# GRBL3-10086.net
KiCad netlist of a schematic drawn in Altium Designer
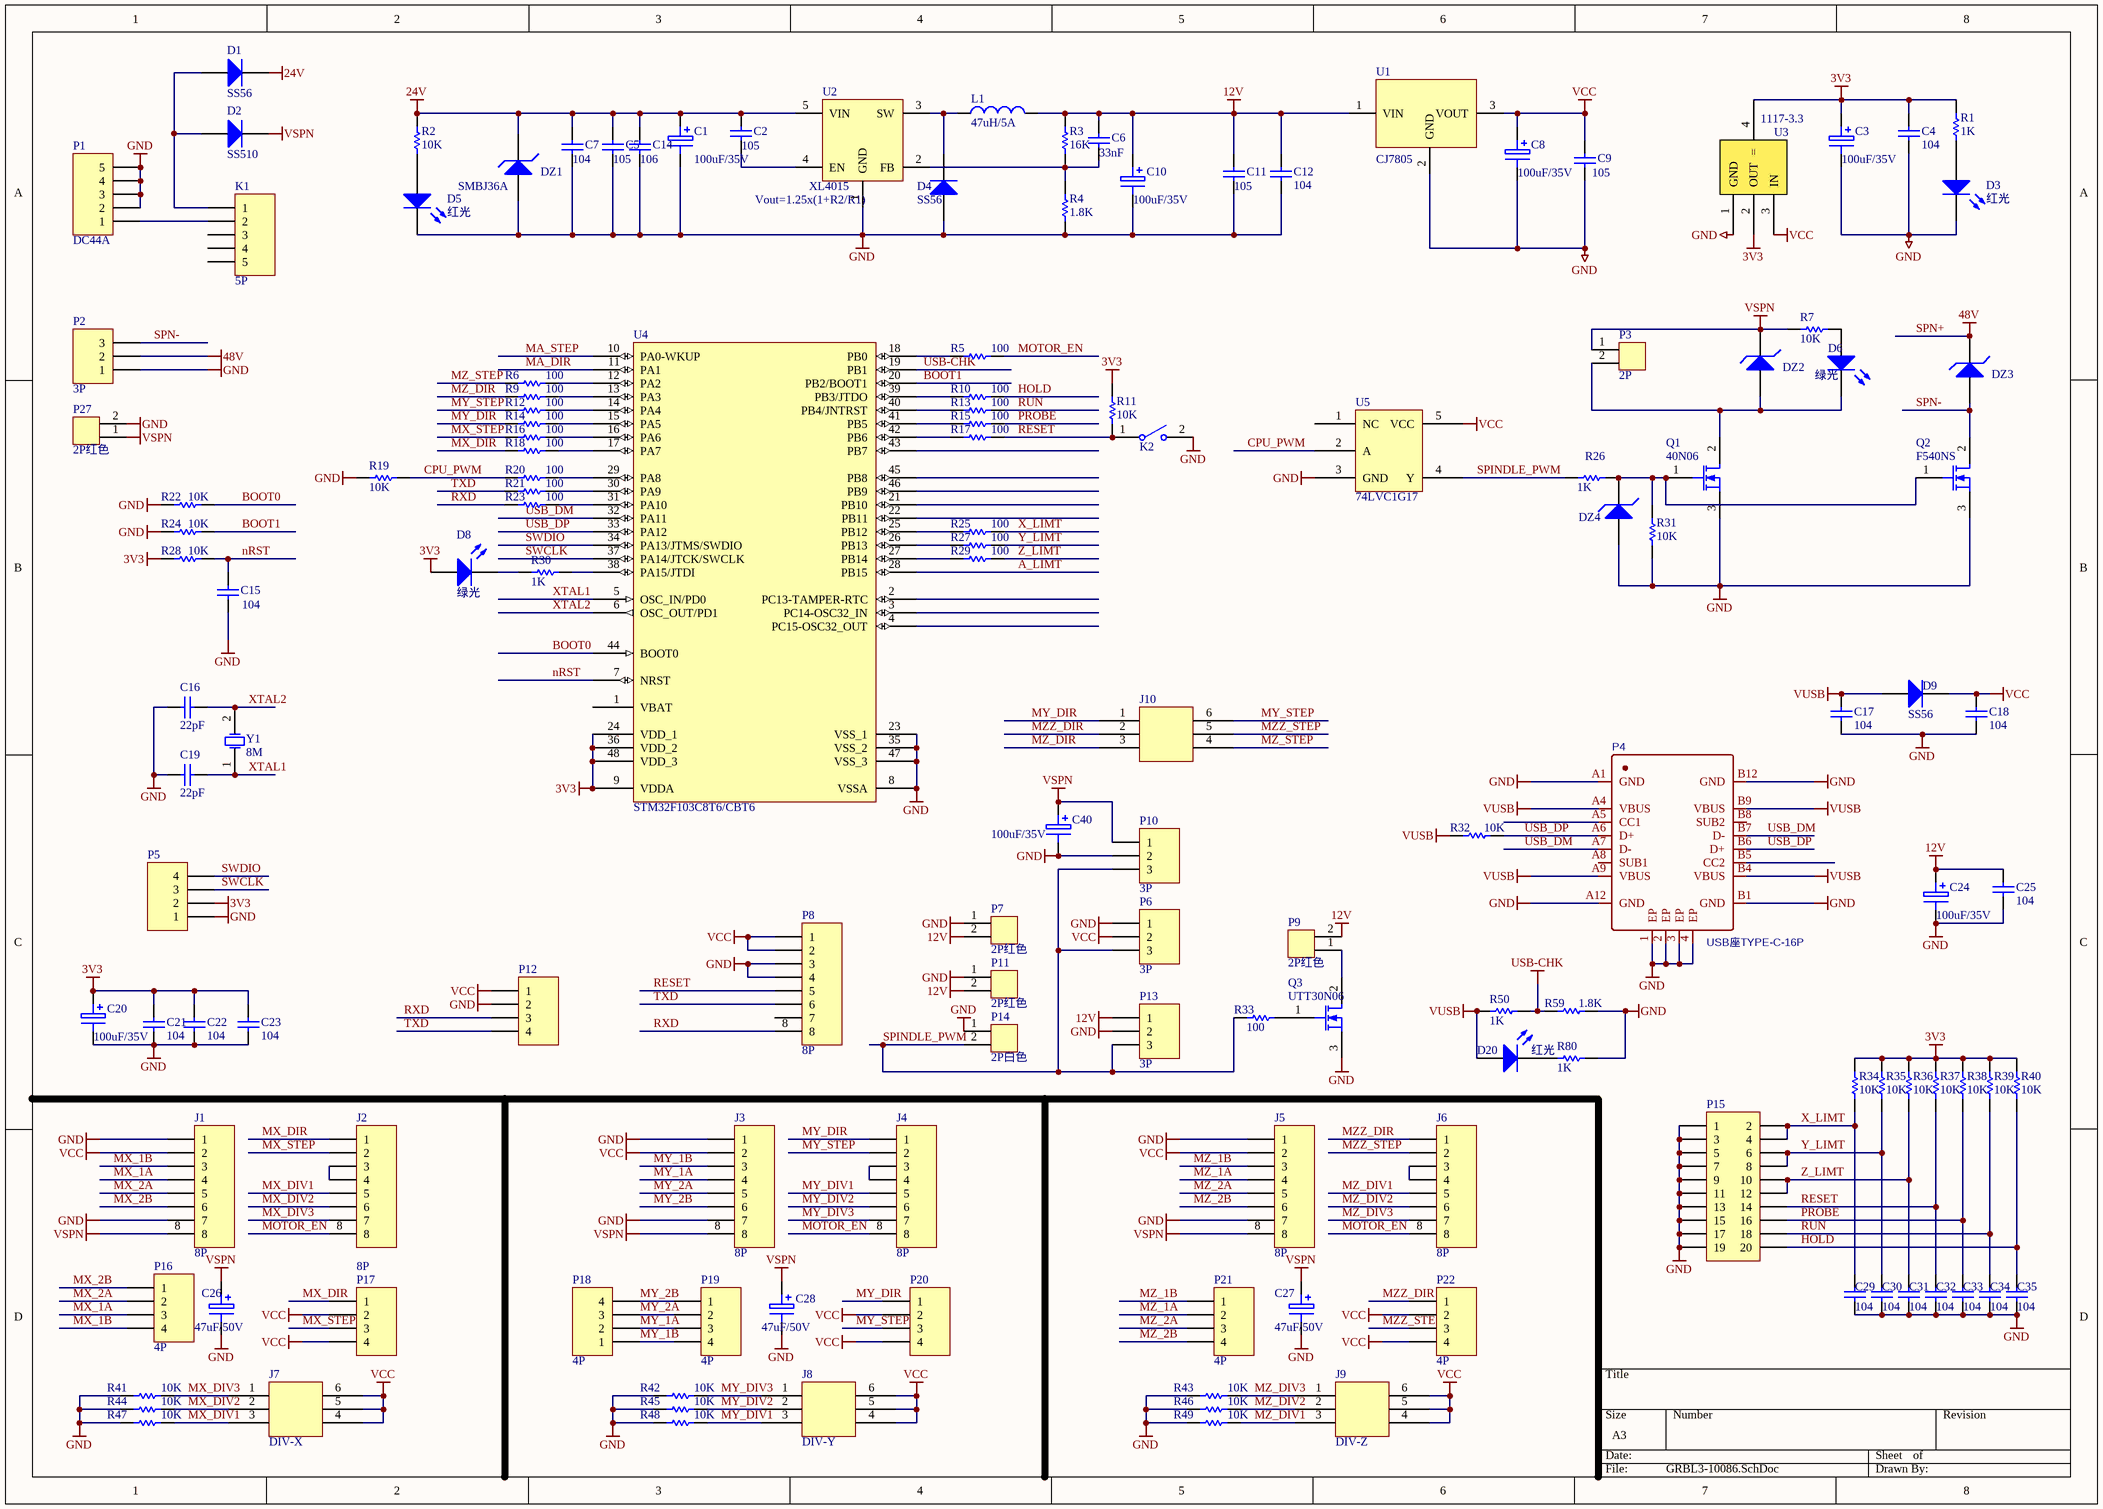
[diagram p0: GRBL3-10086.SchDoc]

(export (version "E")
  (design (tool "Eeschema 10.0.6"))
  (components
    (comp (ref "C1") (value "100uF/35V") (footprint "电解电容贴片6x6") (libsource (lib "*") (part "ELECTRO1")))
    (comp (ref "C2") (value "105") (footprint "0603C") (libsource (lib "SCH封装库") (part "CAP")))
    (comp (ref "C3") (value "100uF/35V") (footprint "电解电容贴片6x6") (libsource (lib "*") (part "ELECTRO1")))
    (comp (ref "C4")
      (value "104")
      (footprint "0603C")
      (description "Capacitor (Semiconductor SIM Model)")
      (fields (field (name "PUBLISHER") "Altium Limited"))
      (libsource (lib "Miscellaneous Devices") (part "Cap Semi"))
    )
    (comp (ref "C5") (value "105") (footprint "0603C") (libsource (lib "SCH封装库") (part "CAP")))
    (comp (ref "C6") (value "33nF") (footprint "0603C") (libsource (lib "SCH封装库") (part "CAP")))
    (comp (ref "C7") (value "104") (footprint "0603C") (libsource (lib "SCH封装库") (part "CAP")))
    (comp (ref "C8") (value "100uF/35V") (footprint "电解电容贴片6x6") (libsource (lib "*") (part "ELECTRO1")))
    (comp (ref "C9")
      (value "105")
      (footprint "0603C")
      (description "Capacitor (Semiconductor SIM Model)")
      (fields (field (name "PUBLISHER") "Altium Limited"))
      (libsource (lib "Miscellaneous Devices") (part "Cap Semi"))
    )
    (comp (ref "C10") (value "100uF/35V") (footprint "电解电容贴片6x6") (libsource (lib "*") (part "ELECTRO1")))
    (comp (ref "C11") (value "105") (footprint "0603C") (libsource (lib "SCH封装库") (part "CAP")))
    (comp (ref "C12")
      (value "104")
      (footprint "0603C")
      (description "Capacitor (Semiconductor SIM Model)")
      (fields (field (name "PUBLISHER") "Altium Limited"))
      (libsource (lib "Miscellaneous Devices") (part "Cap Semi"))
    )
    (comp (ref "C14") (value "106") (footprint "1206C") (libsource (lib "SCH封装库") (part "CAP")))
    (comp (ref "C15")
      (value "104")
      (footprint "0603C")
      (description "Capacitor (Semiconductor SIM Model)")
      (fields (field (name "PUBLISHER") "Altium Limited"))
      (libsource (lib "Miscellaneous Devices") (part "Cap Semi"))
    )
    (comp (ref "C16")
      (value "22pF")
      (footprint "0603C")
      (description "Capacitor (Semiconductor SIM Model)")
      (fields (field (name "PUBLISHER") "Altium Limited"))
      (libsource (lib "Miscellaneous Devices") (part "Cap Semi"))
    )
    (comp (ref "C17")
      (value "104")
      (footprint "0603C")
      (description "Capacitor (Semiconductor SIM Model)")
      (fields (field (name "PUBLISHER") "Altium Limited"))
      (libsource (lib "Miscellaneous Devices") (part "Cap Semi"))
    )
    (comp (ref "C18")
      (value "104")
      (footprint "0603C")
      (description "Capacitor (Semiconductor SIM Model)")
      (fields (field (name "PUBLISHER") "Altium Limited"))
      (libsource (lib "Miscellaneous Devices") (part "Cap Semi"))
    )
    (comp (ref "C19")
      (value "22pF")
      (footprint "0603C")
      (description "Capacitor (Semiconductor SIM Model)")
      (fields (field (name "PUBLISHER") "Altium Limited"))
      (libsource (lib "Miscellaneous Devices") (part "Cap Semi"))
    )
    (comp (ref "C20") (value "100uF/35V") (footprint "电解电容贴片6x6") (libsource (lib "*") (part "ELECTRO1")))
    (comp (ref "C21") (value "104") (footprint "0603C") (libsource (lib "SCH封装库") (part "CAP")))
    (comp (ref "C22") (value "104") (footprint "0603C") (libsource (lib "SCH封装库") (part "CAP")))
    (comp (ref "C23") (value "104") (footprint "0603C") (libsource (lib "SCH封装库") (part "CAP")))
    (comp (ref "C24") (value "100uF/35V") (footprint "电解电容贴片6x6") (libsource (lib "*") (part "ELECTRO1")))
    (comp (ref "C25")
      (value "104")
      (footprint "0603C")
      (description "Capacitor (Semiconductor SIM Model)")
      (fields (field (name "PUBLISHER") "Altium Limited"))
      (libsource (lib "Miscellaneous Devices") (part "Cap Semi"))
    )
    (comp (ref "C26") (value "47uF/50V") (footprint "电解电容贴片6x6") (libsource (lib "*") (part "ELECTRO1")))
    (comp (ref "C27") (value "47uF/50V") (footprint "电解电容贴片6x6") (libsource (lib "*") (part "ELECTRO1")))
    (comp (ref "C28") (value "47uF/50V") (footprint "电解电容贴片6x6") (libsource (lib "*") (part "ELECTRO1")))
    (comp (ref "C29")
      (value "104")
      (footprint "0603C")
      (description "Capacitor (Semiconductor SIM Model)")
      (fields (field (name "PUBLISHER") "Altium Limited"))
      (libsource (lib "Miscellaneous Devices") (part "Cap Semi"))
    )
    (comp (ref "C30")
      (value "104")
      (footprint "0603C")
      (description "Capacitor (Semiconductor SIM Model)")
      (fields (field (name "PUBLISHER") "Altium Limited"))
      (libsource (lib "Miscellaneous Devices") (part "Cap Semi"))
    )
    (comp (ref "C31")
      (value "104")
      (footprint "0603C")
      (description "Capacitor (Semiconductor SIM Model)")
      (fields (field (name "PUBLISHER") "Altium Limited"))
      (libsource (lib "Miscellaneous Devices") (part "Cap Semi"))
    )
    (comp (ref "C32")
      (value "104")
      (footprint "0603C")
      (description "Capacitor (Semiconductor SIM Model)")
      (fields (field (name "PUBLISHER") "Altium Limited"))
      (libsource (lib "Miscellaneous Devices") (part "Cap Semi"))
    )
    (comp (ref "C33")
      (value "104")
      (footprint "0603C")
      (description "Capacitor (Semiconductor SIM Model)")
      (fields (field (name "PUBLISHER") "Altium Limited"))
      (libsource (lib "Miscellaneous Devices") (part "Cap Semi"))
    )
    (comp (ref "C34")
      (value "104")
      (footprint "0603C")
      (description "Capacitor (Semiconductor SIM Model)")
      (fields (field (name "PUBLISHER") "Altium Limited"))
      (libsource (lib "Miscellaneous Devices") (part "Cap Semi"))
    )
    (comp (ref "C35")
      (value "104")
      (footprint "0603C")
      (description "Capacitor (Semiconductor SIM Model)")
      (fields (field (name "PUBLISHER") "Altium Limited"))
      (libsource (lib "Miscellaneous Devices") (part "Cap Semi"))
    )
    (comp (ref "C40") (value "100uF/35V") (footprint "电解电容贴片6x6") (libsource (lib "*") (part "ELECTRO1")))
    (comp (ref "D1") (value "SS56") (footprint "SMA") (libsource (lib "SCH封装库") (part "1N4148")))
    (comp (ref "D2") (value "SS510") (footprint "SMB") (libsource (lib "SCH封装库") (part "1N4148")))
    (comp (ref "D3") (value "红光") (footprint "0603LED") (libsource (lib "SCH封装库") (part "LED")))
    (comp (ref "D4") (value "SS56") (footprint "SMC") (libsource (lib "SCH封装库") (part "1N4148")))
    (comp (ref "D5") (value "红光") (footprint "0603LED") (libsource (lib "SCH封装库") (part "LED")))
    (comp (ref "D6") (value "绿光") (footprint "0603LED") (libsource (lib "SCH封装库") (part "LED")))
    (comp (ref "D8") (value "绿光") (footprint "0603LED") (libsource (lib "SCH封装库") (part "LED")))
    (comp (ref "D9") (value "SS56") (footprint "SMA") (libsource (lib "SCH封装库") (part "1N4148")))
    (comp (ref "D20") (value "红光") (footprint "0603LED") (libsource (lib "SCH封装库") (part "LED")))
    (comp (ref "DZ1") (value "SMBJ36A") (footprint "SMB") (libsource (lib "SCH封装库") (part "稳压二极管")))
    (comp (ref "DZ2") (value "快恢复二极管RS5M") (footprint "SMC") (libsource (lib "SCH封装库") (part "稳压二极管")))
    (comp (ref "DZ3") (value "快恢复二极管RS5M") (footprint "SMC") (libsource (lib "SCH封装库") (part "稳压二极管")))
    (comp (ref "DZ4") (value "稳压二极管SMAZ10V") (footprint "SMA") (libsource (lib "SCH封装库") (part "稳压二极管")))
    (comp (ref "J1") (value "8P") (footprint "HDR1X8") (libsource (lib "SCH封装库") (part "8P")))
    (comp (ref "J2") (value "8P") (footprint "HDR1X8") (libsource (lib "SCH封装库") (part "8P")))
    (comp (ref "J3") (value "8P") (footprint "HDR1X8") (libsource (lib "SCH封装库") (part "8P")))
    (comp (ref "J4") (value "8P") (footprint "HDR1X8") (libsource (lib "SCH封装库") (part "8P")))
    (comp (ref "J5") (value "8P") (footprint "HDR1X8") (libsource (lib "SCH封装库") (part "8P")))
    (comp (ref "J6") (value "8P") (footprint "HDR1X8") (libsource (lib "SCH封装库") (part "8P")))
    (comp (ref "J7") (value "DIV-X") (footprint "HDR2X3") (libsource (lib "SCH封装库") (part "DIP6")))
    (comp (ref "J8") (value "DIV-Y") (footprint "HDR2X3") (libsource (lib "SCH封装库") (part "DIP6")))
    (comp (ref "J9") (value "DIV-Z") (footprint "HDR2X3") (libsource (lib "SCH封装库") (part "DIP6")))
    (comp (ref "J10") (value "DIV-Y") (footprint "HDR2X3") (libsource (lib "SCH封装库") (part "DIP6")))
    (comp (ref "K1") (value "5P") (footprint "拨动开关SS12D11") (libsource (lib "SCH封装库") (part "5P")))
    (comp (ref "K2") (value "开关") (footprint "按键6x6贴片5脚") (libsource (lib "SCH封装库") (part "开关")))
    (comp (ref "L1")
      (value "47uH/5A")
      (footprint "电感贴片12x12")
      (description "Inductor")
      (fields (field (name "PUBLISHER") "Altium Limited"))
      (libsource (lib "SCH封装库") (part "Inductor"))
    )
    (comp (ref "P1")
      (value "DC44A")
      (footprint "DC0044A")
      (description "Header, 5-Pin")
      (fields (field (name "PUBLISHER") "Altium Limited"))
      (libsource (lib "Miscellaneous Connectors") (part "Header 5"))
    )
    (comp (ref "P2") (value "3P") (footprint "直插座3P-KF300") (libsource (lib "") (part "3P_1")))
    (comp (ref "P3") (value "2P") (footprint "VH3.96-2P直插座") (libsource (lib "SCH封装库") (part "2P")))
    (comp (ref "P4")
      (value "USB座TYPE-C-16P")
      (footprint "USB-TYPE-C-16P")
      (fields
        (field (name "BOM_SUPPLIER PART") "C709358")
        (field (name "BOM_MANUFACTURER PART") "KH-TYPE-C-16P-T")
        (field (name "CONTRIBUTOR") "LCSC")
      )
      (libsource (lib "SCH封装库") (part "USB座TYPE-C-16P"))
    )
    (comp (ref "P5") (value "~") (footprint "SIP4") (libsource (lib "") (part "4P_1")))
    (comp (ref "P6") (value "3P") (footprint "SIP3") (libsource (lib "SCH封装库") (part "3P")))
    (comp (ref "P7") (value "2P红色") (footprint "HDR1X2_CON") (libsource (lib "SCH封装库") (part "2P")))
    (comp (ref "P8") (value "8P") (footprint "IDC8") (libsource (lib "SCH封装库") (part "8P")))
    (comp (ref "P9") (value "2P红色") (footprint "HDR1X2_CON") (libsource (lib "") (part "2P_1")))
    (comp (ref "P10") (value "3P") (footprint "HDR1X3_CON") (libsource (lib "SCH封装库") (part "3P")))
    (comp (ref "P11") (value "2P红色") (footprint "HDR1X2_CON") (libsource (lib "SCH封装库") (part "2P")))
    (comp (ref "P12") (value "~") (footprint "SIP4") (libsource (lib "SCH封装库") (part "4P")))
    (comp (ref "P13") (value "3P") (footprint "HDR1X3_CON") (libsource (lib "SCH封装库") (part "3P")))
    (comp (ref "P14") (value "2P白色") (footprint "HDR1X2_CON") (libsource (lib "SCH封装库") (part "2P")))
    (comp (ref "P15")
      (value "Header 10X2H")
      (footprint "HDR2X10")
      (description "Header, 10-Pin, Dual row, Right Angle")
      (fields (field (name "PUBLISHER") "Altium Limited"))
      (libsource (lib "Miscellaneous Connectors") (part "Header 10X2H"))
    )
    (comp (ref "P16") (value "4P") (footprint "HDR1X4_CON") (libsource (lib "SCH封装库") (part "4P")))
    (comp (ref "P17") (value "~") (footprint "SIP4") (libsource (lib "SCH封装库") (part "4P")))
    (comp (ref "P18") (value "4P") (footprint "HDR1X4_CON") (libsource (lib "") (part "4P_1")))
    (comp (ref "P19") (value "4P") (footprint "HDR1X4_CON") (libsource (lib "SCH封装库") (part "4P")))
    (comp (ref "P20") (value "~") (footprint "SIP4") (libsource (lib "SCH封装库") (part "4P")))
    (comp (ref "P21") (value "4P") (footprint "HDR1X4_CON") (libsource (lib "SCH封装库") (part "4P")))
    (comp (ref "P22") (value "4P") (footprint "SIP4") (libsource (lib "SCH封装库") (part "4P")))
    (comp (ref "P27") (value "2P红色") (footprint "HDR1X2_CON") (libsource (lib "") (part "2P_1")))
    (comp (ref "Q1")
      (value "40N06")
      (footprint "TO-252")
      (description "N-Channel MOSFET")
      (fields (field (name "PUBLISHER") "Altium Limited"))
      (libsource (lib "SCH封装库") (part "MOSFET-N"))
    )
    (comp (ref "Q2")
      (value "F540NS")
      (footprint "TO-263-2")
      (description "N-Channel MOSFET")
      (fields (field (name "PUBLISHER") "Altium Limited"))
      (libsource (lib "SCH封装库") (part "MOSFET-N"))
    )
    (comp (ref "Q3")
      (value "UTT30N06")
      (footprint "TO-252")
      (description "N-Channel MOSFET")
      (fields (field (name "PUBLISHER") "Altium Limited"))
      (libsource (lib "SCH封装库") (part "MOSFET-N"))
    )
    (comp (ref "R1")
      (value "1K")
      (footprint "0603R")
      (description "Resistor")
      (fields (field (name "PUBLISHER") "Altium Limited"))
      (libsource (lib "SCH封装库") (part "RES"))
    )
    (comp (ref "R2")
      (value "10K")
      (footprint "0603R")
      (description "Resistor")
      (fields (field (name "PUBLISHER") "Altium Limited"))
      (libsource (lib "SCH封装库") (part "RES"))
    )
    (comp (ref "R3")
      (value "16K")
      (footprint "0603R")
      (description "Resistor")
      (fields (field (name "PUBLISHER") "Altium Limited"))
      (libsource (lib "SCH封装库") (part "RES"))
    )
    (comp (ref "R4")
      (value "1.8K")
      (footprint "0603R")
      (description "Resistor")
      (fields (field (name "PUBLISHER") "Altium Limited"))
      (libsource (lib "SCH封装库") (part "RES"))
    )
    (comp (ref "R5")
      (value "100")
      (footprint "0603R")
      (description "Resistor")
      (fields (field (name "PUBLISHER") "Altium Limited"))
      (libsource (lib "SCH封装库") (part "RES"))
    )
    (comp (ref "R6")
      (value "100")
      (footprint "0603R")
      (description "Resistor")
      (fields (field (name "PUBLISHER") "Altium Limited"))
      (libsource (lib "SCH封装库") (part "RES"))
    )
    (comp (ref "R7")
      (value "10K")
      (footprint "0603R")
      (description "Resistor")
      (fields (field (name "PUBLISHER") "Altium Limited"))
      (libsource (lib "SCH封装库") (part "RES"))
    )
    (comp (ref "R9")
      (value "100")
      (footprint "0603R")
      (description "Resistor")
      (fields (field (name "PUBLISHER") "Altium Limited"))
      (libsource (lib "SCH封装库") (part "RES"))
    )
    (comp (ref "R10")
      (value "100")
      (footprint "0603R")
      (description "Resistor")
      (fields (field (name "PUBLISHER") "Altium Limited"))
      (libsource (lib "SCH封装库") (part "RES"))
    )
    (comp (ref "R11")
      (value "10K")
      (footprint "0603R")
      (description "Resistor")
      (fields (field (name "PUBLISHER") "Altium Limited"))
      (libsource (lib "SCH封装库") (part "RES"))
    )
    (comp (ref "R12")
      (value "100")
      (footprint "0603R")
      (description "Resistor")
      (fields (field (name "PUBLISHER") "Altium Limited"))
      (libsource (lib "SCH封装库") (part "RES"))
    )
    (comp (ref "R13")
      (value "100")
      (footprint "0603R")
      (description "Resistor")
      (fields (field (name "PUBLISHER") "Altium Limited"))
      (libsource (lib "SCH封装库") (part "RES"))
    )
    (comp (ref "R14")
      (value "100")
      (footprint "0603R")
      (description "Resistor")
      (fields (field (name "PUBLISHER") "Altium Limited"))
      (libsource (lib "SCH封装库") (part "RES"))
    )
    (comp (ref "R15")
      (value "100")
      (footprint "0603R")
      (description "Resistor")
      (fields (field (name "PUBLISHER") "Altium Limited"))
      (libsource (lib "SCH封装库") (part "RES"))
    )
    (comp (ref "R16")
      (value "100")
      (footprint "0603R")
      (description "Resistor")
      (fields (field (name "PUBLISHER") "Altium Limited"))
      (libsource (lib "SCH封装库") (part "RES"))
    )
    (comp (ref "R17")
      (value "100")
      (footprint "0603R")
      (description "Resistor")
      (fields (field (name "PUBLISHER") "Altium Limited"))
      (libsource (lib "SCH封装库") (part "RES"))
    )
    (comp (ref "R18")
      (value "100")
      (footprint "0603R")
      (description "Resistor")
      (fields (field (name "PUBLISHER") "Altium Limited"))
      (libsource (lib "SCH封装库") (part "RES"))
    )
    (comp (ref "R19")
      (value "10K")
      (footprint "0603R")
      (description "Resistor")
      (fields (field (name "PUBLISHER") "Altium Limited"))
      (libsource (lib "SCH封装库") (part "RES"))
    )
    (comp (ref "R20")
      (value "100")
      (footprint "0603R")
      (description "Resistor")
      (fields (field (name "PUBLISHER") "Altium Limited"))
      (libsource (lib "SCH封装库") (part "RES"))
    )
    (comp (ref "R21")
      (value "100")
      (footprint "0603R")
      (description "Resistor")
      (fields (field (name "PUBLISHER") "Altium Limited"))
      (libsource (lib "SCH封装库") (part "RES"))
    )
    (comp (ref "R22")
      (value "10K")
      (footprint "0603R")
      (description "Resistor")
      (fields (field (name "Comment") "10k") (field (name "PUBLISHER") "Altium Limited"))
      (libsource (lib "SCH封装库") (part "RES"))
    )
    (comp (ref "R23")
      (value "100")
      (footprint "0603R")
      (description "Resistor")
      (fields (field (name "PUBLISHER") "Altium Limited"))
      (libsource (lib "SCH封装库") (part "RES"))
    )
    (comp (ref "R24")
      (value "10K")
      (footprint "0603R")
      (description "Resistor")
      (fields (field (name "Comment") "10k") (field (name "PUBLISHER") "Altium Limited"))
      (libsource (lib "SCH封装库") (part "RES"))
    )
    (comp (ref "R25")
      (value "100")
      (footprint "0603R")
      (description "Resistor")
      (fields (field (name "PUBLISHER") "Altium Limited"))
      (libsource (lib "SCH封装库") (part "RES"))
    )
    (comp (ref "R26")
      (value "1K")
      (footprint "0603R")
      (description "Resistor")
      (fields (field (name "PUBLISHER") "Altium Limited"))
      (libsource (lib "SCH封装库") (part "RES"))
    )
    (comp (ref "R27")
      (value "100")
      (footprint "0603R")
      (description "Resistor")
      (fields (field (name "PUBLISHER") "Altium Limited"))
      (libsource (lib "SCH封装库") (part "RES"))
    )
    (comp (ref "R28")
      (value "10K")
      (footprint "0603R")
      (description "Resistor")
      (fields (field (name "Comment") "10k") (field (name "PUBLISHER") "Altium Limited"))
      (libsource (lib "SCH封装库") (part "RES"))
    )
    (comp (ref "R29")
      (value "100")
      (footprint "0603R")
      (description "Resistor")
      (fields (field (name "PUBLISHER") "Altium Limited"))
      (libsource (lib "SCH封装库") (part "RES"))
    )
    (comp (ref "R30")
      (value "1K")
      (footprint "0603R")
      (description "Resistor")
      (fields (field (name "PUBLISHER") "Altium Limited"))
      (libsource (lib "SCH封装库") (part "RES"))
    )
    (comp (ref "R31")
      (value "10K")
      (footprint "0603R")
      (description "Resistor")
      (fields (field (name "PUBLISHER") "Altium Limited"))
      (libsource (lib "SCH封装库") (part "RES"))
    )
    (comp (ref "R32")
      (value "10K")
      (footprint "0603R")
      (description "Resistor")
      (fields (field (name "PUBLISHER") "Altium Limited"))
      (libsource (lib "SCH封装库") (part "RES"))
    )
    (comp (ref "R33")
      (value "100")
      (footprint "0603R")
      (description "Resistor")
      (fields (field (name "PUBLISHER") "Altium Limited"))
      (libsource (lib "SCH封装库") (part "RES"))
    )
    (comp (ref "R34")
      (value "10K")
      (footprint "0603R")
      (description "Resistor")
      (fields (field (name "PUBLISHER") "Altium Limited"))
      (libsource (lib "SCH封装库") (part "RES"))
    )
    (comp (ref "R35")
      (value "10K")
      (footprint "0603R")
      (description "Resistor")
      (fields (field (name "PUBLISHER") "Altium Limited"))
      (libsource (lib "SCH封装库") (part "RES"))
    )
    (comp (ref "R36")
      (value "10K")
      (footprint "0603R")
      (description "Resistor")
      (fields (field (name "PUBLISHER") "Altium Limited"))
      (libsource (lib "SCH封装库") (part "RES"))
    )
    (comp (ref "R37")
      (value "10K")
      (footprint "0603R")
      (description "Resistor")
      (fields (field (name "PUBLISHER") "Altium Limited"))
      (libsource (lib "SCH封装库") (part "RES"))
    )
    (comp (ref "R38")
      (value "10K")
      (footprint "0603R")
      (description "Resistor")
      (fields (field (name "PUBLISHER") "Altium Limited"))
      (libsource (lib "SCH封装库") (part "RES"))
    )
    (comp (ref "R39")
      (value "10K")
      (footprint "0603R")
      (description "Resistor")
      (fields (field (name "PUBLISHER") "Altium Limited"))
      (libsource (lib "SCH封装库") (part "RES"))
    )
    (comp (ref "R40")
      (value "10K")
      (footprint "0603R")
      (description "Resistor")
      (fields (field (name "PUBLISHER") "Altium Limited"))
      (libsource (lib "SCH封装库") (part "RES"))
    )
    (comp (ref "R41")
      (value "10K")
      (footprint "0603R")
      (description "Resistor")
      (fields (field (name "PUBLISHER") "Altium Limited"))
      (libsource (lib "SCH封装库") (part "RES"))
    )
    (comp (ref "R42")
      (value "10K")
      (footprint "0603R")
      (description "Resistor")
      (fields (field (name "PUBLISHER") "Altium Limited"))
      (libsource (lib "SCH封装库") (part "RES"))
    )
    (comp (ref "R43")
      (value "10K")
      (footprint "0603R")
      (description "Resistor")
      (fields (field (name "PUBLISHER") "Altium Limited"))
      (libsource (lib "SCH封装库") (part "RES"))
    )
    (comp (ref "R44")
      (value "10K")
      (footprint "0603R")
      (description "Resistor")
      (fields (field (name "PUBLISHER") "Altium Limited"))
      (libsource (lib "SCH封装库") (part "RES"))
    )
    (comp (ref "R45")
      (value "10K")
      (footprint "0603R")
      (description "Resistor")
      (fields (field (name "PUBLISHER") "Altium Limited"))
      (libsource (lib "SCH封装库") (part "RES"))
    )
    (comp (ref "R46")
      (value "10K")
      (footprint "0603R")
      (description "Resistor")
      (fields (field (name "PUBLISHER") "Altium Limited"))
      (libsource (lib "SCH封装库") (part "RES"))
    )
    (comp (ref "R47")
      (value "10K")
      (footprint "0603R")
      (description "Resistor")
      (fields (field (name "PUBLISHER") "Altium Limited"))
      (libsource (lib "SCH封装库") (part "RES"))
    )
    (comp (ref "R48")
      (value "10K")
      (footprint "0603R")
      (description "Resistor")
      (fields (field (name "PUBLISHER") "Altium Limited"))
      (libsource (lib "SCH封装库") (part "RES"))
    )
    (comp (ref "R49")
      (value "10K")
      (footprint "0603R")
      (description "Resistor")
      (fields (field (name "PUBLISHER") "Altium Limited"))
      (libsource (lib "SCH封装库") (part "RES"))
    )
    (comp (ref "R50")
      (value "1K")
      (footprint "0603R")
      (description "Resistor")
      (fields (field (name "PUBLISHER") "Altium Limited"))
      (libsource (lib "SCH封装库") (part "RES"))
    )
    (comp (ref "R59")
      (value "1.8K")
      (footprint "0603R")
      (description "Resistor")
      (fields (field (name "PUBLISHER") "Altium Limited"))
      (libsource (lib "SCH封装库") (part "RES"))
    )
    (comp (ref "R80")
      (value "1K")
      (footprint "0603R")
      (description "Resistor")
      (fields (field (name "PUBLISHER") "Altium Limited"))
      (libsource (lib "SCH封装库") (part "RES"))
    )
    (comp (ref "U1") (value "CJ7805") (footprint "TO-263-2") (libsource (lib "SCH封装库") (part "7805")))
    (comp (ref "U2") (value "XL4015") (footprint "TO-263") (libsource (lib "SCH封装库") (part "XL4005")))
    (comp (ref "U3") (value "1117-3.3") (footprint "SOT-223") (libsource (lib "Party600") (part "LM1117")))
    (comp (ref "U4")
      (value "STM32F103C8T6/CBT6")
      (footprint "LQFP48")
      (description "STM32 ARM-based 32-bit MCU with 32 Kbytes Flash, 48-pin LQFP, Industrial Temperature")
      (fields (field (name "PUBLISHER") "*"))
      (libsource (lib "ST Microcontroller 32-Bit STM32 SCH") (part "STM32F103C6T6"))
    )
    (comp (ref "U5") (value "74LVC1G17") (footprint "SOT-23-5") (libsource (lib "SCH封装库") (part "74LVC1G17")))
    (comp (ref "Y1")
      (value "8M")
      (footprint "晶振贴片")
      (description "Crystal Oscillator")
      (fields (field (name "PUBLISHER") "Altium Limited"))
      (libsource (lib "Miscellaneous Devices") (part "XTAL"))
    )
  )
  (nets
    (net (code "1") (name "/A_LIMT") (class "Default")
      (node (ref "U4") (pin "28") (pinfunction "PB15_28") (pintype "bidirectional"))
    )
    (net (code "2") (name "/BOOT0") (class "Default")
      (node (ref "R22") (pin "2") (pinfunction "2_2") (pintype "passive"))
      (node (ref "U4") (pin "44") (pinfunction "BOOT0_44") (pintype "input"))
    )
    (net (code "3") (name "/BOOT1") (class "Default")
      (node (ref "R24") (pin "2") (pinfunction "2_2") (pintype "passive"))
      (node (ref "U4") (pin "20") (pinfunction "PB2/BOOT1_20") (pintype "bidirectional"))
    )
    (net (code "4") (name "/CPU_PWM") (class "Default")
      (node (ref "R19") (pin "1") (pinfunction "1_1") (pintype "passive"))
      (node (ref "R20") (pin "1") (pinfunction "1_1") (pintype "passive"))
      (node (ref "U5") (pin "2") (pinfunction "A_2") (pintype "passive"))
    )
    (net (code "5") (name "/HOLD") (class "Default")
      (node (ref "C35") (pin "2") (pinfunction "2_2") (pintype "passive"))
      (node (ref "P15") (pin "20") (pinfunction "20_20") (pintype "passive"))
      (node (ref "R10") (pin "2") (pinfunction "2_2") (pintype "passive"))
      (node (ref "R40") (pin "1") (pinfunction "1_1") (pintype "passive"))
    )
    (net (code "6") (name "/MA_DIR") (class "Default")
      (node (ref "U4") (pin "11") (pinfunction "PA1_11") (pintype "bidirectional"))
    )
    (net (code "7") (name "/MA_STEP") (class "Default")
      (node (ref "U4") (pin "10") (pinfunction "PA0-WKUP_10") (pintype "bidirectional"))
    )
    (net (code "8") (name "/MOTOR_EN") (class "Default")
      (node (ref "J2") (pin "8") (pinfunction "8_8") (pintype "passive"))
      (node (ref "J4") (pin "8") (pinfunction "8_8") (pintype "passive"))
      (node (ref "J6") (pin "8") (pinfunction "8_8") (pintype "passive"))
      (node (ref "R5") (pin "2") (pinfunction "2_2") (pintype "passive"))
    )
    (net (code "9") (name "/MX_1A") (class "Default")
      (node (ref "J1") (pin "4") (pinfunction "4_4") (pintype "passive"))
      (node (ref "P16") (pin "3") (pinfunction "3_3") (pintype "passive"))
    )
    (net (code "10") (name "/MX_1B") (class "Default")
      (node (ref "J1") (pin "3") (pinfunction "3_3") (pintype "passive"))
      (node (ref "P16") (pin "4") (pinfunction "4_4") (pintype "passive"))
    )
    (net (code "11") (name "/MX_2A") (class "Default")
      (node (ref "J1") (pin "5") (pinfunction "5_5") (pintype "passive"))
      (node (ref "P16") (pin "2") (pinfunction "2_2") (pintype "passive"))
    )
    (net (code "12") (name "/MX_2B") (class "Default")
      (node (ref "J1") (pin "6") (pinfunction "6_6") (pintype "passive"))
      (node (ref "P16") (pin "1") (pinfunction "1_1") (pintype "passive"))
    )
    (net (code "13") (name "/MX_DIR") (class "Default")
      (node (ref "J2") (pin "1") (pinfunction "1_1") (pintype "passive"))
      (node (ref "P17") (pin "1") (pinfunction "1_1") (pintype "passive"))
      (node (ref "R18") (pin "1") (pinfunction "1_1") (pintype "passive"))
    )
    (net (code "14") (name "/MX_DIV1") (class "Default")
      (node (ref "J2") (pin "5") (pinfunction "5_5") (pintype "passive"))
      (node (ref "J7") (pin "3") (pinfunction "3_3") (pintype "passive"))
      (node (ref "R47") (pin "1") (pinfunction "1_1") (pintype "passive"))
    )
    (net (code "15") (name "/MX_DIV2") (class "Default")
      (node (ref "J2") (pin "6") (pinfunction "6_6") (pintype "passive"))
      (node (ref "J7") (pin "2") (pinfunction "2_2") (pintype "passive"))
      (node (ref "R44") (pin "1") (pinfunction "1_1") (pintype "passive"))
    )
    (net (code "16") (name "/MX_DIV3") (class "Default")
      (node (ref "J2") (pin "7") (pinfunction "7_7") (pintype "passive"))
      (node (ref "J7") (pin "1") (pinfunction "1_1") (pintype "passive"))
      (node (ref "R41") (pin "1") (pinfunction "1_1") (pintype "passive"))
    )
    (net (code "17") (name "/MX_STEP") (class "Default")
      (node (ref "J2") (pin "2") (pinfunction "2_2") (pintype "passive"))
      (node (ref "P17") (pin "3") (pinfunction "3_3") (pintype "passive"))
      (node (ref "R16") (pin "1") (pinfunction "1_1") (pintype "passive"))
    )
    (net (code "18") (name "/MY_1A") (class "Default")
      (node (ref "J3") (pin "4") (pinfunction "4_4") (pintype "passive"))
      (node (ref "P18") (pin "2") (pinfunction "2_2") (pintype "passive"))
      (node (ref "P19") (pin "3") (pinfunction "3_3") (pintype "passive"))
    )
    (net (code "19") (name "/MY_1B") (class "Default")
      (node (ref "J3") (pin "3") (pinfunction "3_3") (pintype "passive"))
      (node (ref "P18") (pin "1") (pinfunction "1_1") (pintype "passive"))
      (node (ref "P19") (pin "4") (pinfunction "4_4") (pintype "passive"))
    )
    (net (code "20") (name "/MY_2A") (class "Default")
      (node (ref "J3") (pin "5") (pinfunction "5_5") (pintype "passive"))
      (node (ref "P18") (pin "3") (pinfunction "3_3") (pintype "passive"))
      (node (ref "P19") (pin "2") (pinfunction "2_2") (pintype "passive"))
    )
    (net (code "21") (name "/MY_2B") (class "Default")
      (node (ref "J3") (pin "6") (pinfunction "6_6") (pintype "passive"))
      (node (ref "P18") (pin "4") (pinfunction "4_4") (pintype "passive"))
      (node (ref "P19") (pin "1") (pinfunction "1_1") (pintype "passive"))
    )
    (net (code "22") (name "/MY_DIR") (class "Default")
      (node (ref "J10") (pin "1") (pinfunction "1_1") (pintype "passive"))
      (node (ref "J4") (pin "1") (pinfunction "1_1") (pintype "passive"))
      (node (ref "P20") (pin "1") (pinfunction "1_1") (pintype "passive"))
      (node (ref "R14") (pin "1") (pinfunction "1_1") (pintype "passive"))
    )
    (net (code "23") (name "/MY_DIV1") (class "Default")
      (node (ref "J4") (pin "5") (pinfunction "5_5") (pintype "passive"))
      (node (ref "J8") (pin "3") (pinfunction "3_3") (pintype "passive"))
      (node (ref "R48") (pin "1") (pinfunction "1_1") (pintype "passive"))
    )
    (net (code "24") (name "/MY_DIV2") (class "Default")
      (node (ref "J4") (pin "6") (pinfunction "6_6") (pintype "passive"))
      (node (ref "J8") (pin "2") (pinfunction "2_2") (pintype "passive"))
      (node (ref "R45") (pin "1") (pinfunction "1_1") (pintype "passive"))
    )
    (net (code "25") (name "/MY_DIV3") (class "Default")
      (node (ref "J4") (pin "7") (pinfunction "7_7") (pintype "passive"))
      (node (ref "J8") (pin "1") (pinfunction "1_1") (pintype "passive"))
      (node (ref "R42") (pin "1") (pinfunction "1_1") (pintype "passive"))
    )
    (net (code "26") (name "/MY_STEP") (class "Default")
      (node (ref "J10") (pin "6") (pinfunction "6_6") (pintype "passive"))
      (node (ref "J4") (pin "2") (pinfunction "2_2") (pintype "passive"))
      (node (ref "P20") (pin "3") (pinfunction "3_3") (pintype "passive"))
      (node (ref "R12") (pin "1") (pinfunction "1_1") (pintype "passive"))
    )
    (net (code "27") (name "/MZZ_DIR") (class "Default")
      (node (ref "J10") (pin "2") (pinfunction "2_2") (pintype "passive"))
      (node (ref "J6") (pin "1") (pinfunction "1_1") (pintype "passive"))
      (node (ref "P22") (pin "1") (pinfunction "1_1") (pintype "passive"))
    )
    (net (code "28") (name "/MZZ_STEP") (class "Default")
      (node (ref "J10") (pin "5") (pinfunction "5_5") (pintype "passive"))
      (node (ref "J6") (pin "2") (pinfunction "2_2") (pintype "passive"))
      (node (ref "P22") (pin "3") (pinfunction "3_3") (pintype "passive"))
    )
    (net (code "29") (name "/MZ_1A") (class "Default")
      (node (ref "J5") (pin "4") (pinfunction "4_4") (pintype "passive"))
      (node (ref "P21") (pin "2") (pinfunction "2_2") (pintype "passive"))
    )
    (net (code "30") (name "/MZ_1B") (class "Default")
      (node (ref "J5") (pin "3") (pinfunction "3_3") (pintype "passive"))
      (node (ref "P21") (pin "1") (pinfunction "1_1") (pintype "passive"))
    )
    (net (code "31") (name "/MZ_2A") (class "Default")
      (node (ref "J5") (pin "5") (pinfunction "5_5") (pintype "passive"))
      (node (ref "P21") (pin "3") (pinfunction "3_3") (pintype "passive"))
    )
    (net (code "32") (name "/MZ_2B") (class "Default")
      (node (ref "J5") (pin "6") (pinfunction "6_6") (pintype "passive"))
      (node (ref "P21") (pin "4") (pinfunction "4_4") (pintype "passive"))
    )
    (net (code "33") (name "/MZ_DIR") (class "Default")
      (node (ref "J10") (pin "3") (pinfunction "3_3") (pintype "passive"))
      (node (ref "R9") (pin "1") (pinfunction "1_1") (pintype "passive"))
    )
    (net (code "34") (name "/MZ_DIV1") (class "Default")
      (node (ref "J6") (pin "5") (pinfunction "5_5") (pintype "passive"))
      (node (ref "J9") (pin "3") (pinfunction "3_3") (pintype "passive"))
      (node (ref "R49") (pin "1") (pinfunction "1_1") (pintype "passive"))
    )
    (net (code "35") (name "/MZ_DIV2") (class "Default")
      (node (ref "J6") (pin "6") (pinfunction "6_6") (pintype "passive"))
      (node (ref "J9") (pin "2") (pinfunction "2_2") (pintype "passive"))
      (node (ref "R46") (pin "1") (pinfunction "1_1") (pintype "passive"))
    )
    (net (code "36") (name "/MZ_DIV3") (class "Default")
      (node (ref "J6") (pin "7") (pinfunction "7_7") (pintype "passive"))
      (node (ref "J9") (pin "1") (pinfunction "1_1") (pintype "passive"))
      (node (ref "R43") (pin "1") (pinfunction "1_1") (pintype "passive"))
    )
    (net (code "37") (name "/MZ_STEP") (class "Default")
      (node (ref "J10") (pin "4") (pinfunction "4_4") (pintype "passive"))
      (node (ref "R6") (pin "1") (pinfunction "1_1") (pintype "passive"))
    )
    (net (code "38") (name "/PROBE") (class "Default")
      (node (ref "C33") (pin "2") (pinfunction "2_2") (pintype "passive"))
      (node (ref "P15") (pin "16") (pinfunction "16_16") (pintype "passive"))
      (node (ref "R15") (pin "2") (pinfunction "2_2") (pintype "passive"))
      (node (ref "R38") (pin "1") (pinfunction "1_1") (pintype "passive"))
    )
    (net (code "39") (name "/RESET") (class "Default")
      (node (ref "C32") (pin "2") (pinfunction "2_2") (pintype "passive"))
      (node (ref "K2") (pin "1") (pinfunction "COMMON_1") (pintype "passive"))
      (node (ref "P15") (pin "14") (pinfunction "14_14") (pintype "passive"))
      (node (ref "P8") (pin "5") (pinfunction "5_5") (pintype "passive"))
      (node (ref "R11") (pin "1") (pinfunction "1_1") (pintype "passive"))
      (node (ref "R17") (pin "2") (pinfunction "2_2") (pintype "passive"))
      (node (ref "R37") (pin "1") (pinfunction "1_1") (pintype "passive"))
    )
    (net (code "40") (name "/RUN") (class "Default")
      (node (ref "C34") (pin "2") (pinfunction "2_2") (pintype "passive"))
      (node (ref "P15") (pin "18") (pinfunction "18_18") (pintype "passive"))
      (node (ref "R13") (pin "2") (pinfunction "2_2") (pintype "passive"))
      (node (ref "R39") (pin "1") (pinfunction "1_1") (pintype "passive"))
    )
    (net (code "41") (name "/RXD") (class "Default")
      (node (ref "P12") (pin "3") (pinfunction "3_3") (pintype "passive"))
      (node (ref "P8") (pin "8") (pinfunction "8_8") (pintype "passive"))
      (node (ref "R23") (pin "1") (pinfunction "1_1") (pintype "passive"))
    )
    (net (code "42") (name "/SPINDLE_PWM") (class "Default")
      (node (ref "P10") (pin "3") (pinfunction "3_3") (pintype "passive"))
      (node (ref "P13") (pin "3") (pinfunction "3_3") (pintype "passive"))
      (node (ref "P14") (pin "2") (pintype "passive"))
      (node (ref "P6") (pin "3") (pinfunction "3_3") (pintype "passive"))
      (node (ref "R26") (pin "1") (pinfunction "1_1") (pintype "passive"))
      (node (ref "R33") (pin "1") (pinfunction "1_1") (pintype "passive"))
      (node (ref "U5") (pin "4") (pinfunction "Y_4") (pintype "passive"))
    )
    (net (code "43") (name "/SPN-") (class "Default")
      (node (ref "DZ3") (pin "1") (pinfunction "1_1") (pintype "passive"))
      (node (ref "P2") (pin "3") (pinfunction "3_3") (pintype "passive"))
      (node (ref "Q2") (pin "2") (pinfunction "D_2") (pintype "passive"))
    )
    (net (code "44") (name "/SWCLK") (class "Default")
      (node (ref "P5") (pin "3") (pinfunction "3_3") (pintype "passive"))
      (node (ref "U4") (pin "37") (pinfunction "PA14/JTCK/SWCLK_37") (pintype "bidirectional"))
    )
    (net (code "45") (name "/SWDIO") (class "Default")
      (node (ref "P5") (pin "4") (pinfunction "4_4") (pintype "passive"))
      (node (ref "U4") (pin "34") (pinfunction "PA13/JTMS/SWDIO_34") (pintype "bidirectional"))
    )
    (net (code "46") (name "/TXD") (class "Default")
      (node (ref "P12") (pin "4") (pinfunction "4_4") (pintype "passive"))
      (node (ref "P8") (pin "6") (pinfunction "6_6") (pintype "passive"))
      (node (ref "R21") (pin "1") (pinfunction "1_1") (pintype "passive"))
    )
    (net (code "47") (name "/USB_DM") (class "Default")
      (node (ref "P4") (pin "A7") (pinfunction "D-_A7") (pintype "passive"))
      (node (ref "P4") (pin "B7") (pinfunction "D-_B7") (pintype "passive"))
      (node (ref "U4") (pin "32") (pinfunction "PA11_32") (pintype "bidirectional"))
    )
    (net (code "48") (name "/USB_DP") (class "Default")
      (node (ref "P4") (pin "A6") (pinfunction "D+_A6") (pintype "passive"))
      (node (ref "P4") (pin "B6") (pinfunction "D+_B6") (pintype "passive"))
      (node (ref "R32") (pin "2") (pinfunction "2_2") (pintype "passive"))
      (node (ref "U4") (pin "33") (pinfunction "PA12_33") (pintype "bidirectional"))
    )
    (net (code "49") (name "/XTAL1") (class "Default")
      (node (ref "C19") (pin "1") (pinfunction "1_1") (pintype "passive"))
      (node (ref "U4") (pin "5") (pinfunction "OSC_IN/PD0_5") (pintype "input"))
      (node (ref "Y1") (pin "1") (pinfunction "OSC1_1") (pintype "passive"))
    )
    (net (code "50") (name "/XTAL2") (class "Default")
      (node (ref "C16") (pin "1") (pinfunction "1_1") (pintype "passive"))
      (node (ref "U4") (pin "6") (pinfunction "OSC_OUT/PD1_6") (pintype "output"))
      (node (ref "Y1") (pin "2") (pinfunction "OSC2_2") (pintype "passive"))
    )
    (net (code "51") (name "/X_LIMT") (class "Default")
      (node (ref "C29") (pin "2") (pinfunction "2_2") (pintype "passive"))
      (node (ref "P15") (pin "2") (pinfunction "2_2") (pintype "passive"))
      (node (ref "P15") (pin "4") (pinfunction "4_4") (pintype "passive"))
      (node (ref "R25") (pin "2") (pinfunction "2_2") (pintype "passive"))
      (node (ref "R34") (pin "1") (pinfunction "1_1") (pintype "passive"))
    )
    (net (code "52") (name "/Y_LIMT") (class "Default")
      (node (ref "C30") (pin "2") (pinfunction "2_2") (pintype "passive"))
      (node (ref "P15") (pin "6") (pinfunction "6_6") (pintype "passive"))
      (node (ref "P15") (pin "8") (pinfunction "8_8") (pintype "passive"))
      (node (ref "R27") (pin "2") (pinfunction "2_2") (pintype "passive"))
      (node (ref "R35") (pin "1") (pinfunction "1_1") (pintype "passive"))
    )
    (net (code "53") (name "/Z_LIMT") (class "Default")
      (node (ref "C31") (pin "2") (pinfunction "2_2") (pintype "passive"))
      (node (ref "P15") (pin "10") (pinfunction "10_10") (pintype "passive"))
      (node (ref "P15") (pin "12") (pinfunction "12_12") (pintype "passive"))
      (node (ref "R29") (pin "2") (pinfunction "2_2") (pintype "passive"))
      (node (ref "R36") (pin "1") (pinfunction "1_1") (pintype "passive"))
    )
    (net (code "54") (name "/nRST") (class "Default")
      (node (ref "C15") (pin "2") (pinfunction "2_2") (pintype "passive"))
      (node (ref "R28") (pin "2") (pinfunction "2_2") (pintype "passive"))
      (node (ref "U4") (pin "7") (pinfunction "NRST_7") (pintype "bidirectional"))
    )
    (net (code "55") (name "3V3") (class "Default")
      (node (ref "C20") (pin "1") (pintype "passive"))
      (node (ref "C21") (pin "2") (pinfunction "2_2") (pintype "passive"))
      (node (ref "C22") (pin "2") (pinfunction "2_2") (pintype "passive"))
      (node (ref "C23") (pin "2") (pinfunction "2_2") (pintype "passive"))
      (node (ref "C3") (pin "1") (pintype "passive"))
      (node (ref "C4") (pin "2") (pinfunction "2_2") (pintype "passive"))
      (node (ref "D8") (pin "1") (pinfunction "1_1") (pintype "passive"))
      (node (ref "P5") (pin "2") (pinfunction "2_2") (pintype "passive"))
      (node (ref "R1") (pin "1") (pinfunction "1_1") (pintype "passive"))
      (node (ref "R11") (pin "2") (pinfunction "2_2") (pintype "passive"))
      (node (ref "R28") (pin "1") (pinfunction "1_1") (pintype "passive"))
      (node (ref "R34") (pin "2") (pinfunction "2_2") (pintype "passive"))
      (node (ref "R35") (pin "2") (pinfunction "2_2") (pintype "passive"))
      (node (ref "R36") (pin "2") (pinfunction "2_2") (pintype "passive"))
      (node (ref "R37") (pin "2") (pinfunction "2_2") (pintype "passive"))
      (node (ref "R38") (pin "2") (pinfunction "2_2") (pintype "passive"))
      (node (ref "R39") (pin "2") (pinfunction "2_2") (pintype "passive"))
      (node (ref "R40") (pin "2") (pinfunction "2_2") (pintype "passive"))
      (node (ref "U3") (pin "2") (pinfunction "OUT_2") (pintype "power_in"))
      (node (ref "U3") (pin "4") (pinfunction "=_4") (pintype "power_in"))
      (node (ref "U4") (pin "24") (pinfunction "VDD_1_24") (pintype "power_in"))
      (node (ref "U4") (pin "36") (pinfunction "VDD_2_36") (pintype "power_in"))
      (node (ref "U4") (pin "48") (pinfunction "VDD_3_48") (pintype "power_in"))
      (node (ref "U4") (pin "9") (pinfunction "VDDA_9") (pintype "power_in"))
    )
    (net (code "56") (name "12V") (class "Default")
      (node (ref "C10") (pin "1") (pintype "passive"))
      (node (ref "C11") (pin "2") (pinfunction "2_2") (pintype "passive"))
      (node (ref "C12") (pin "2") (pinfunction "2_2") (pintype "passive"))
      (node (ref "C24") (pin "1") (pintype "passive"))
      (node (ref "C25") (pin "2") (pinfunction "2_2") (pintype "passive"))
      (node (ref "C6") (pin "2") (pinfunction "2_2") (pintype "passive"))
      (node (ref "L1") (pin "2") (pinfunction "2_2") (pintype "passive"))
      (node (ref "P11") (pin "2") (pintype "passive"))
      (node (ref "P13") (pin "1") (pinfunction "1_1") (pintype "passive"))
      (node (ref "P7") (pin "2") (pintype "passive"))
      (node (ref "P9") (pin "2") (pintype "passive"))
      (node (ref "R3") (pin "2") (pinfunction "2_2") (pintype "passive"))
      (node (ref "U1") (pin "1") (pinfunction "VIN_1") (pintype "passive"))
    )
    (net (code "57") (name "24V") (class "Default")
      (node (ref "C1") (pin "1") (pintype "passive"))
      (node (ref "C14") (pin "2") (pinfunction "2_2") (pintype "passive"))
      (node (ref "C2") (pin "2") (pinfunction "2_2") (pintype "passive"))
      (node (ref "C5") (pin "2") (pinfunction "2_2") (pintype "passive"))
      (node (ref "C7") (pin "2") (pinfunction "2_2") (pintype "passive"))
      (node (ref "D1") (pin "2") (pinfunction "2_2") (pintype "passive"))
      (node (ref "DZ1") (pin "2") (pinfunction "2_2") (pintype "passive"))
      (node (ref "R2") (pin "1") (pinfunction "1_1") (pintype "passive"))
      (node (ref "U2") (pin "5") (pinfunction "VIN_5") (pintype "passive"))
    )
    (net (code "58") (name "48V") (class "Default")
      (node (ref "DZ3") (pin "2") (pinfunction "2_2") (pintype "passive"))
      (node (ref "P2") (pin "2") (pinfunction "2_2") (pintype "passive"))
    )
    (net (code "59") (name "GND") (class "Default")
      (node (ref "C1") (pin "2") (pintype "passive"))
      (node (ref "C10") (pin "2") (pintype "passive"))
      (node (ref "C11") (pin "1") (pinfunction "1_1") (pintype "passive"))
      (node (ref "C12") (pin "1") (pinfunction "1_1") (pintype "passive"))
      (node (ref "C14") (pin "1") (pinfunction "1_1") (pintype "passive"))
      (node (ref "C15") (pin "1") (pinfunction "1_1") (pintype "passive"))
      (node (ref "C16") (pin "2") (pinfunction "2_2") (pintype "passive"))
      (node (ref "C17") (pin "1") (pinfunction "1_1") (pintype "passive"))
      (node (ref "C18") (pin "1") (pinfunction "1_1") (pintype "passive"))
      (node (ref "C19") (pin "2") (pinfunction "2_2") (pintype "passive"))
      (node (ref "C20") (pin "2") (pintype "passive"))
      (node (ref "C21") (pin "1") (pinfunction "1_1") (pintype "passive"))
      (node (ref "C22") (pin "1") (pinfunction "1_1") (pintype "passive"))
      (node (ref "C23") (pin "1") (pinfunction "1_1") (pintype "passive"))
      (node (ref "C24") (pin "2") (pintype "passive"))
      (node (ref "C25") (pin "1") (pinfunction "1_1") (pintype "passive"))
      (node (ref "C26") (pin "2") (pintype "passive"))
      (node (ref "C27") (pin "2") (pintype "passive"))
      (node (ref "C28") (pin "2") (pintype "passive"))
      (node (ref "C29") (pin "1") (pinfunction "1_1") (pintype "passive"))
      (node (ref "C3") (pin "2") (pintype "passive"))
      (node (ref "C30") (pin "1") (pinfunction "1_1") (pintype "passive"))
      (node (ref "C31") (pin "1") (pinfunction "1_1") (pintype "passive"))
      (node (ref "C32") (pin "1") (pinfunction "1_1") (pintype "passive"))
      (node (ref "C33") (pin "1") (pinfunction "1_1") (pintype "passive"))
      (node (ref "C34") (pin "1") (pinfunction "1_1") (pintype "passive"))
      (node (ref "C35") (pin "1") (pinfunction "1_1") (pintype "passive"))
      (node (ref "C4") (pin "1") (pinfunction "1_1") (pintype "passive"))
      (node (ref "C40") (pin "2") (pintype "passive"))
      (node (ref "C5") (pin "1") (pinfunction "1_1") (pintype "passive"))
      (node (ref "C7") (pin "1") (pinfunction "1_1") (pintype "passive"))
      (node (ref "C8") (pin "2") (pintype "passive"))
      (node (ref "C9") (pin "1") (pinfunction "1_1") (pintype "passive"))
      (node (ref "D3") (pin "2") (pinfunction "2_2") (pintype "passive"))
      (node (ref "D4") (pin "1") (pinfunction "1_1") (pintype "passive"))
      (node (ref "D5") (pin "2") (pinfunction "2_2") (pintype "passive"))
      (node (ref "DZ1") (pin "1") (pinfunction "1_1") (pintype "passive"))
      (node (ref "DZ4") (pin "1") (pinfunction "1_1") (pintype "passive"))
      (node (ref "J1") (pin "1") (pinfunction "1_1") (pintype "passive"))
      (node (ref "J1") (pin "7") (pinfunction "7_7") (pintype "passive"))
      (node (ref "J3") (pin "1") (pinfunction "1_1") (pintype "passive"))
      (node (ref "J3") (pin "7") (pinfunction "7_7") (pintype "passive"))
      (node (ref "J5") (pin "1") (pinfunction "1_1") (pintype "passive"))
      (node (ref "J5") (pin "7") (pinfunction "7_7") (pintype "passive"))
      (node (ref "K2") (pin "2") (pinfunction "NO_2") (pintype "passive"))
      (node (ref "P1") (pin "2") (pinfunction "2_2") (pintype "passive"))
      (node (ref "P1") (pin "3") (pinfunction "3_3") (pintype "passive"))
      (node (ref "P1") (pin "4") (pinfunction "4_4") (pintype "passive"))
      (node (ref "P1") (pin "5") (pinfunction "5_5") (pintype "passive"))
      (node (ref "P10") (pin "2") (pinfunction "2_2") (pintype "passive"))
      (node (ref "P11") (pin "1") (pintype "passive"))
      (node (ref "P12") (pin "2") (pinfunction "2_2") (pintype "passive"))
      (node (ref "P13") (pin "2") (pinfunction "2_2") (pintype "passive"))
      (node (ref "P14") (pin "1") (pintype "passive"))
      (node (ref "P15") (pin "1") (pinfunction "1_1") (pintype "passive"))
      (node (ref "P15") (pin "11") (pinfunction "11_11") (pintype "passive"))
      (node (ref "P15") (pin "13") (pinfunction "13_13") (pintype "passive"))
      (node (ref "P15") (pin "15") (pinfunction "15_15") (pintype "passive"))
      (node (ref "P15") (pin "17") (pinfunction "17_17") (pintype "passive"))
      (node (ref "P15") (pin "19") (pinfunction "19_19") (pintype "passive"))
      (node (ref "P15") (pin "3") (pinfunction "3_3") (pintype "passive"))
      (node (ref "P15") (pin "5") (pinfunction "5_5") (pintype "passive"))
      (node (ref "P15") (pin "7") (pinfunction "7_7") (pintype "passive"))
      (node (ref "P15") (pin "9") (pinfunction "9_9") (pintype "passive"))
      (node (ref "P2") (pin "1") (pinfunction "1_1") (pintype "passive"))
      (node (ref "P27") (pin "2") (pintype "passive"))
      (node (ref "P4") (pin "1") (pinfunction "EP_1") (pintype "passive"))
      (node (ref "P4") (pin "2") (pinfunction "EP_2") (pintype "passive"))
      (node (ref "P4") (pin "3") (pinfunction "EP_3") (pintype "passive"))
      (node (ref "P4") (pin "4") (pinfunction "EP_4") (pintype "passive"))
      (node (ref "P4") (pin "A1") (pinfunction "GND_A1") (pintype "passive"))
      (node (ref "P4") (pin "A12") (pinfunction "GND_A12") (pintype "passive"))
      (node (ref "P4") (pin "B1") (pinfunction "GND_B1") (pintype "passive"))
      (node (ref "P4") (pin "B12") (pinfunction "GND_B12") (pintype "passive"))
      (node (ref "P5") (pin "1") (pinfunction "1_1") (pintype "passive"))
      (node (ref "P6") (pin "1") (pinfunction "1_1") (pintype "passive"))
      (node (ref "P7") (pin "1") (pintype "passive"))
      (node (ref "P8") (pin "3") (pinfunction "3_3") (pintype "passive"))
      (node (ref "P8") (pin "4") (pinfunction "4_4") (pintype "passive"))
      (node (ref "Q1") (pin "3") (pinfunction "S_3") (pintype "passive"))
      (node (ref "Q2") (pin "3") (pinfunction "S_3") (pintype "passive"))
      (node (ref "Q3") (pin "3") (pinfunction "S_3") (pintype "passive"))
      (node (ref "R19") (pin "2") (pinfunction "2_2") (pintype "passive"))
      (node (ref "R22") (pin "1") (pinfunction "1_1") (pintype "passive"))
      (node (ref "R24") (pin "1") (pinfunction "1_1") (pintype "passive"))
      (node (ref "R31") (pin "2") (pinfunction "2_2") (pintype "passive"))
      (node (ref "R4") (pin "1") (pinfunction "1_1") (pintype "passive"))
      (node (ref "R41") (pin "2") (pinfunction "2_2") (pintype "passive"))
      (node (ref "R42") (pin "2") (pinfunction "2_2") (pintype "passive"))
      (node (ref "R43") (pin "2") (pinfunction "2_2") (pintype "passive"))
      (node (ref "R44") (pin "2") (pinfunction "2_2") (pintype "passive"))
      (node (ref "R45") (pin "2") (pinfunction "2_2") (pintype "passive"))
      (node (ref "R46") (pin "2") (pinfunction "2_2") (pintype "passive"))
      (node (ref "R47") (pin "2") (pinfunction "2_2") (pintype "passive"))
      (node (ref "R48") (pin "2") (pinfunction "2_2") (pintype "passive"))
      (node (ref "R49") (pin "2") (pinfunction "2_2") (pintype "passive"))
      (node (ref "R59") (pin "2") (pinfunction "2_2") (pintype "passive"))
      (node (ref "R80") (pin "1") (pinfunction "1_1") (pintype "passive"))
      (node (ref "U1") (pin "2") (pinfunction "GND_2") (pintype "passive"))
      (node (ref "U2") (pin "1") (pinfunction "GND_1") (pintype "passive"))
      (node (ref "U3") (pin "1") (pinfunction "GND_1") (pintype "power_in"))
      (node (ref "U4") (pin "23") (pinfunction "VSS_1_23") (pintype "power_in"))
      (node (ref "U4") (pin "35") (pinfunction "VSS_2_35") (pintype "power_in"))
      (node (ref "U4") (pin "47") (pinfunction "VSS_3_47") (pintype "power_in"))
      (node (ref "U4") (pin "8") (pinfunction "VSSA_8") (pintype "power_in"))
      (node (ref "U5") (pin "3") (pinfunction "GND_3") (pintype "passive"))
    )
    (net (code "60") (name "Net-(D1-Pad1)") (class "Default")
      (node (ref "D1") (pin "1") (pinfunction "1_1") (pintype "passive"))
      (node (ref "D2") (pin "1") (pinfunction "1_1") (pintype "passive"))
      (node (ref "K1") (pin "1") (pinfunction "1_1") (pintype "passive"))
    )
    (net (code "61") (name "Net-(D3-Pad1)") (class "Default")
      (node (ref "D3") (pin "1") (pinfunction "1_1") (pintype "passive"))
      (node (ref "R1") (pin "2") (pinfunction "2_2") (pintype "passive"))
    )
    (net (code "62") (name "Net-(D5-Pad1)") (class "Default")
      (node (ref "D5") (pin "1") (pinfunction "1_1") (pintype "passive"))
      (node (ref "R2") (pin "2") (pinfunction "2_2") (pintype "passive"))
    )
    (net (code "63") (name "Net-(D6-Pad1)") (class "Default")
      (node (ref "D6") (pin "1") (pinfunction "1_1") (pintype "passive"))
      (node (ref "R7") (pin "2") (pinfunction "2_2") (pintype "passive"))
    )
    (net (code "64") (name "Net-(D8-Pad2)") (class "Default")
      (node (ref "D8") (pin "2") (pinfunction "2_2") (pintype "passive"))
      (node (ref "R30") (pin "2") (pinfunction "2_2") (pintype "passive"))
    )
    (net (code "65") (name "Net-(D20-Pad2)") (class "Default")
      (node (ref "D20") (pin "2") (pinfunction "2_2") (pintype "passive"))
      (node (ref "R80") (pin "2") (pinfunction "2_2") (pintype "passive"))
    )
    (net (code "66") (name "Net-(J2-Pad3)") (class "Default")
      (node (ref "J2") (pin "3") (pinfunction "3_3") (pintype "passive"))
      (node (ref "J2") (pin "4") (pinfunction "4_4") (pintype "passive"))
    )
    (net (code "67") (name "Net-(J4-Pad3)") (class "Default")
      (node (ref "J4") (pin "3") (pinfunction "3_3") (pintype "passive"))
      (node (ref "J4") (pin "4") (pinfunction "4_4") (pintype "passive"))
    )
    (net (code "68") (name "Net-(J6-Pad3)") (class "Default")
      (node (ref "J6") (pin "3") (pinfunction "3_3") (pintype "passive"))
      (node (ref "J6") (pin "4") (pinfunction "4_4") (pintype "passive"))
    )
    (net (code "69") (name "Net-(K1-Pad2)") (class "Default")
      (node (ref "K1") (pin "2") (pinfunction "2_2") (pintype "passive"))
      (node (ref "P1") (pin "1") (pinfunction "1_1") (pintype "passive"))
    )
    (net (code "70") (name "Net-(Q1-D)") (class "Default")
      (node (ref "D6") (pin "2") (pinfunction "2_2") (pintype "passive"))
      (node (ref "DZ2") (pin "1") (pinfunction "1_1") (pintype "passive"))
      (node (ref "P3") (pin "2") (pintype "passive"))
      (node (ref "Q1") (pin "2") (pinfunction "D_2") (pintype "passive"))
    )
    (net (code "71") (name "Net-(Q1-G)") (class "Default")
      (node (ref "DZ4") (pin "2") (pinfunction "2_2") (pintype "passive"))
      (node (ref "Q1") (pin "1") (pinfunction "G_1") (pintype "passive"))
      (node (ref "Q2") (pin "1") (pinfunction "G_1") (pintype "passive"))
      (node (ref "R26") (pin "2") (pinfunction "2_2") (pintype "passive"))
      (node (ref "R31") (pin "1") (pinfunction "1_1") (pintype "passive"))
    )
    (net (code "72") (name "Net-(Q3-D)") (class "Default")
      (node (ref "P9") (pin "1") (pintype "passive"))
      (node (ref "Q3") (pin "2") (pinfunction "D_2") (pintype "passive"))
    )
    (net (code "73") (name "Net-(Q3-G)") (class "Default")
      (node (ref "Q3") (pin "1") (pinfunction "G_1") (pintype "passive"))
      (node (ref "R33") (pin "2") (pinfunction "2_2") (pintype "passive"))
    )
    (net (code "74") (name "Net-(U2-EN)") (class "Default")
      (node (ref "C2") (pin "1") (pinfunction "1_1") (pintype "passive"))
      (node (ref "U2") (pin "4") (pinfunction "EN_4") (pintype "passive"))
    )
    (net (code "75") (name "Net-(U2-FB)") (class "Default")
      (node (ref "C6") (pin "1") (pinfunction "1_1") (pintype "passive"))
      (node (ref "R3") (pin "1") (pinfunction "1_1") (pintype "passive"))
      (node (ref "R4") (pin "2") (pinfunction "2_2") (pintype "passive"))
      (node (ref "U2") (pin "2") (pinfunction "FB_2") (pintype "passive"))
    )
    (net (code "76") (name "Net-(U2-SW)") (class "Default")
      (node (ref "D4") (pin "2") (pinfunction "2_2") (pintype "passive"))
      (node (ref "L1") (pin "1") (pinfunction "1_1") (pintype "passive"))
      (node (ref "U2") (pin "3") (pinfunction "SW_3") (pintype "passive"))
    )
    (net (code "77") (name "Net-(U4-PA2)") (class "Default")
      (node (ref "R6") (pin "2") (pinfunction "2_2") (pintype "passive"))
      (node (ref "U4") (pin "12") (pinfunction "PA2_12") (pintype "bidirectional"))
    )
    (net (code "78") (name "Net-(U4-PA3)") (class "Default")
      (node (ref "R9") (pin "2") (pinfunction "2_2") (pintype "passive"))
      (node (ref "U4") (pin "13") (pinfunction "PA3_13") (pintype "bidirectional"))
    )
    (net (code "79") (name "Net-(U4-PA4)") (class "Default")
      (node (ref "R12") (pin "2") (pinfunction "2_2") (pintype "passive"))
      (node (ref "U4") (pin "14") (pinfunction "PA4_14") (pintype "bidirectional"))
    )
    (net (code "80") (name "Net-(U4-PA5)") (class "Default")
      (node (ref "R14") (pin "2") (pinfunction "2_2") (pintype "passive"))
      (node (ref "U4") (pin "15") (pinfunction "PA5_15") (pintype "bidirectional"))
    )
    (net (code "81") (name "Net-(U4-PA6)") (class "Default")
      (node (ref "R16") (pin "2") (pinfunction "2_2") (pintype "passive"))
      (node (ref "U4") (pin "16") (pinfunction "PA6_16") (pintype "bidirectional"))
    )
    (net (code "82") (name "Net-(U4-PA7)") (class "Default")
      (node (ref "R18") (pin "2") (pinfunction "2_2") (pintype "passive"))
      (node (ref "U4") (pin "17") (pinfunction "PA7_17") (pintype "bidirectional"))
    )
    (net (code "83") (name "Net-(U4-PA8)") (class "Default")
      (node (ref "R20") (pin "2") (pinfunction "2_2") (pintype "passive"))
      (node (ref "U4") (pin "29") (pinfunction "PA8_29") (pintype "bidirectional"))
    )
    (net (code "84") (name "Net-(U4-PA9)") (class "Default")
      (node (ref "R21") (pin "2") (pinfunction "2_2") (pintype "passive"))
      (node (ref "U4") (pin "30") (pinfunction "PA9_30") (pintype "bidirectional"))
    )
    (net (code "85") (name "Net-(U4-PA10)") (class "Default")
      (node (ref "R23") (pin "2") (pinfunction "2_2") (pintype "passive"))
      (node (ref "U4") (pin "31") (pinfunction "PA10_31") (pintype "bidirectional"))
    )
    (net (code "86") (name "Net-(U4-PA15{slash}JTDI)") (class "Default")
      (node (ref "R30") (pin "1") (pinfunction "1_1") (pintype "passive"))
      (node (ref "U4") (pin "38") (pinfunction "PA15/JTDI_38") (pintype "bidirectional"))
    )
    (net (code "87") (name "Net-(U4-PB0)") (class "Default")
      (node (ref "R5") (pin "1") (pinfunction "1_1") (pintype "passive"))
      (node (ref "U4") (pin "18") (pinfunction "PB0_18") (pintype "bidirectional"))
    )
    (net (code "88") (name "Net-(U4-PB3{slash}JTDO)") (class "Default")
      (node (ref "R10") (pin "1") (pinfunction "1_1") (pintype "passive"))
      (node (ref "U4") (pin "39") (pinfunction "PB3/JTDO_39") (pintype "bidirectional"))
    )
    (net (code "89") (name "Net-(U4-PB4{slash}JNTRST)") (class "Default")
      (node (ref "R13") (pin "1") (pinfunction "1_1") (pintype "passive"))
      (node (ref "U4") (pin "40") (pinfunction "PB4/JNTRST_40") (pintype "bidirectional"))
    )
    (net (code "90") (name "Net-(U4-PB5)") (class "Default")
      (node (ref "R15") (pin "1") (pinfunction "1_1") (pintype "passive"))
      (node (ref "U4") (pin "41") (pinfunction "PB5_41") (pintype "bidirectional"))
    )
    (net (code "91") (name "Net-(U4-PB6)") (class "Default")
      (node (ref "R17") (pin "1") (pinfunction "1_1") (pintype "passive"))
      (node (ref "U4") (pin "42") (pinfunction "PB6_42") (pintype "bidirectional"))
    )
    (net (code "92") (name "Net-(U4-PB12)") (class "Default")
      (node (ref "R25") (pin "1") (pinfunction "1_1") (pintype "passive"))
      (node (ref "U4") (pin "25") (pinfunction "PB12_25") (pintype "bidirectional"))
    )
    (net (code "93") (name "Net-(U4-PB13)") (class "Default")
      (node (ref "R27") (pin "1") (pinfunction "1_1") (pintype "passive"))
      (node (ref "U4") (pin "26") (pinfunction "PB13_26") (pintype "bidirectional"))
    )
    (net (code "94") (name "Net-(U4-PB14)") (class "Default")
      (node (ref "R29") (pin "1") (pinfunction "1_1") (pintype "passive"))
      (node (ref "U4") (pin "27") (pinfunction "PB14_27") (pintype "bidirectional"))
    )
    (net (code "95") (name "USB-CHK") (class "Default")
      (node (ref "R50") (pin "2") (pinfunction "2_2") (pintype "passive"))
      (node (ref "R59") (pin "1") (pinfunction "1_1") (pintype "passive"))
      (node (ref "U4") (pin "19") (pinfunction "PB1_19") (pintype "bidirectional"))
    )
    (net (code "96") (name "VCC") (class "Default")
      (node (ref "C18") (pin "2") (pinfunction "2_2") (pintype "passive"))
      (node (ref "C8") (pin "1") (pintype "passive"))
      (node (ref "C9") (pin "2") (pinfunction "2_2") (pintype "passive"))
      (node (ref "D9") (pin "2") (pinfunction "2_2") (pintype "passive"))
      (node (ref "J1") (pin "2") (pinfunction "2_2") (pintype "passive"))
      (node (ref "J3") (pin "2") (pinfunction "2_2") (pintype "passive"))
      (node (ref "J5") (pin "2") (pinfunction "2_2") (pintype "passive"))
      (node (ref "J7") (pin "4") (pinfunction "4_4") (pintype "passive"))
      (node (ref "J7") (pin "5") (pinfunction "5_5") (pintype "passive"))
      (node (ref "J7") (pin "6") (pinfunction "6_6") (pintype "passive"))
      (node (ref "J8") (pin "4") (pinfunction "4_4") (pintype "passive"))
      (node (ref "J8") (pin "5") (pinfunction "5_5") (pintype "passive"))
      (node (ref "J8") (pin "6") (pinfunction "6_6") (pintype "passive"))
      (node (ref "J9") (pin "4") (pinfunction "4_4") (pintype "passive"))
      (node (ref "J9") (pin "5") (pinfunction "5_5") (pintype "passive"))
      (node (ref "J9") (pin "6") (pinfunction "6_6") (pintype "passive"))
      (node (ref "P12") (pin "1") (pinfunction "1_1") (pintype "passive"))
      (node (ref "P17") (pin "2") (pinfunction "2_2") (pintype "passive"))
      (node (ref "P17") (pin "4") (pinfunction "4_4") (pintype "passive"))
      (node (ref "P20") (pin "2") (pinfunction "2_2") (pintype "passive"))
      (node (ref "P20") (pin "4") (pinfunction "4_4") (pintype "passive"))
      (node (ref "P22") (pin "2") (pinfunction "2_2") (pintype "passive"))
      (node (ref "P22") (pin "4") (pinfunction "4_4") (pintype "passive"))
      (node (ref "P6") (pin "2") (pinfunction "2_2") (pintype "passive"))
      (node (ref "P8") (pin "1") (pinfunction "1_1") (pintype "passive"))
      (node (ref "P8") (pin "2") (pinfunction "2_2") (pintype "passive"))
      (node (ref "U1") (pin "3") (pinfunction "VOUT_3") (pintype "passive"))
      (node (ref "U3") (pin "3") (pinfunction "IN_3") (pintype "power_in"))
      (node (ref "U5") (pin "5") (pinfunction "VCC_5") (pintype "passive"))
    )
    (net (code "97") (name "VSPN") (class "Default")
      (node (ref "C26") (pin "1") (pintype "passive"))
      (node (ref "C27") (pin "1") (pintype "passive"))
      (node (ref "C28") (pin "1") (pintype "passive"))
      (node (ref "C40") (pin "1") (pintype "passive"))
      (node (ref "D2") (pin "2") (pinfunction "2_2") (pintype "passive"))
      (node (ref "DZ2") (pin "2") (pinfunction "2_2") (pintype "passive"))
      (node (ref "J1") (pin "8") (pinfunction "8_8") (pintype "passive"))
      (node (ref "J3") (pin "8") (pinfunction "8_8") (pintype "passive"))
      (node (ref "J5") (pin "8") (pinfunction "8_8") (pintype "passive"))
      (node (ref "P10") (pin "1") (pinfunction "1_1") (pintype "passive"))
      (node (ref "P27") (pin "1") (pintype "passive"))
      (node (ref "P3") (pin "1") (pintype "passive"))
      (node (ref "R7") (pin "1") (pinfunction "1_1") (pintype "passive"))
    )
    (net (code "98") (name "VUSB") (class "Default")
      (node (ref "C17") (pin "2") (pinfunction "2_2") (pintype "passive"))
      (node (ref "D20") (pin "1") (pinfunction "1_1") (pintype "passive"))
      (node (ref "D9") (pin "1") (pinfunction "1_1") (pintype "passive"))
      (node (ref "P4") (pin "A4") (pinfunction "VBUS_A4") (pintype "passive"))
      (node (ref "P4") (pin "A9") (pinfunction "VBUS_A9") (pintype "passive"))
      (node (ref "P4") (pin "B4") (pinfunction "VBUS_B4") (pintype "passive"))
      (node (ref "P4") (pin "B9") (pinfunction "VBUS_B9") (pintype "passive"))
      (node (ref "R32") (pin "1") (pinfunction "1_1") (pintype "passive"))
      (node (ref "R50") (pin "1") (pinfunction "1_1") (pintype "passive"))
    )
    (net (code "99") (name "unconnected-(K1-Pad3)") (class "Default")
      (node (ref "K1") (pin "3") (pinfunction "3_3") (pintype "passive"))
    )
    (net (code "100") (name "unconnected-(K1-Pad4)") (class "Default")
      (node (ref "K1") (pin "4") (pinfunction "4_4") (pintype "passive"))
    )
    (net (code "101") (name "unconnected-(K1-Pad5)") (class "Default")
      (node (ref "K1") (pin "5") (pinfunction "5_5") (pintype "passive"))
    )
    (net (code "102") (name "unconnected-(P4-CC1-PadA5)") (class "Default")
      (node (ref "P4") (pin "A5") (pinfunction "CC1_A5") (pintype "passive"))
    )
    (net (code "103") (name "unconnected-(P4-CC2-PadB5)") (class "Default")
      (node (ref "P4") (pin "B5") (pinfunction "CC2_B5") (pintype "passive"))
    )
    (net (code "104") (name "unconnected-(P4-SUB1-PadA8)") (class "Default")
      (node (ref "P4") (pin "A8") (pinfunction "SUB1_A8") (pintype "passive"))
    )
    (net (code "105") (name "unconnected-(P4-SUB2-PadB8)") (class "Default")
      (node (ref "P4") (pin "B8") (pinfunction "SUB2_B8") (pintype "passive"))
    )
    (net (code "106") (name "unconnected-(P8-Pad7)") (class "Default")
      (node (ref "P8") (pin "7") (pinfunction "7_7") (pintype "passive"))
    )
    (net (code "107") (name "unconnected-(U4-PB7-Pad43)") (class "Default")
      (node (ref "U4") (pin "43") (pinfunction "PB7_43") (pintype "bidirectional"))
    )
    (net (code "108") (name "unconnected-(U4-PB8-Pad45)") (class "Default")
      (node (ref "U4") (pin "45") (pinfunction "PB8_45") (pintype "bidirectional"))
    )
    (net (code "109") (name "unconnected-(U4-PB9-Pad46)") (class "Default")
      (node (ref "U4") (pin "46") (pinfunction "PB9_46") (pintype "bidirectional"))
    )
    (net (code "110") (name "unconnected-(U4-PB10-Pad21)") (class "Default")
      (node (ref "U4") (pin "21") (pinfunction "PB10_21") (pintype "bidirectional"))
    )
    (net (code "111") (name "unconnected-(U4-PB11-Pad22)") (class "Default")
      (node (ref "U4") (pin "22") (pinfunction "PB11_22") (pintype "bidirectional"))
    )
    (net (code "112") (name "unconnected-(U4-PC13-TAMPER-RTC-Pad2)") (class "Default")
      (node (ref "U4") (pin "2") (pinfunction "PC13-TAMPER-RTC_2") (pintype "bidirectional"))
    )
    (net (code "113") (name "unconnected-(U4-PC14-OSC32_IN-Pad3)") (class "Default")
      (node (ref "U4") (pin "3") (pinfunction "PC14-OSC32_IN_3") (pintype "bidirectional"))
    )
    (net (code "114") (name "unconnected-(U4-PC15-OSC32_OUT-Pad4)") (class "Default")
      (node (ref "U4") (pin "4") (pinfunction "PC15-OSC32_OUT_4") (pintype "bidirectional"))
    )
    (net (code "115") (name "unconnected-(U4-VBAT-Pad1)") (class "Default")
      (node (ref "U4") (pin "1") (pinfunction "VBAT_1") (pintype "power_in"))
    )
    (net (code "116") (name "unconnected-(U5-NC-Pad1)") (class "Default")
      (node (ref "U5") (pin "1") (pinfunction "NC_1") (pintype "passive"))
    )
  )
)
